# Audio_MIC.net
KiCad netlist of a schematic drawn in Altium Designer
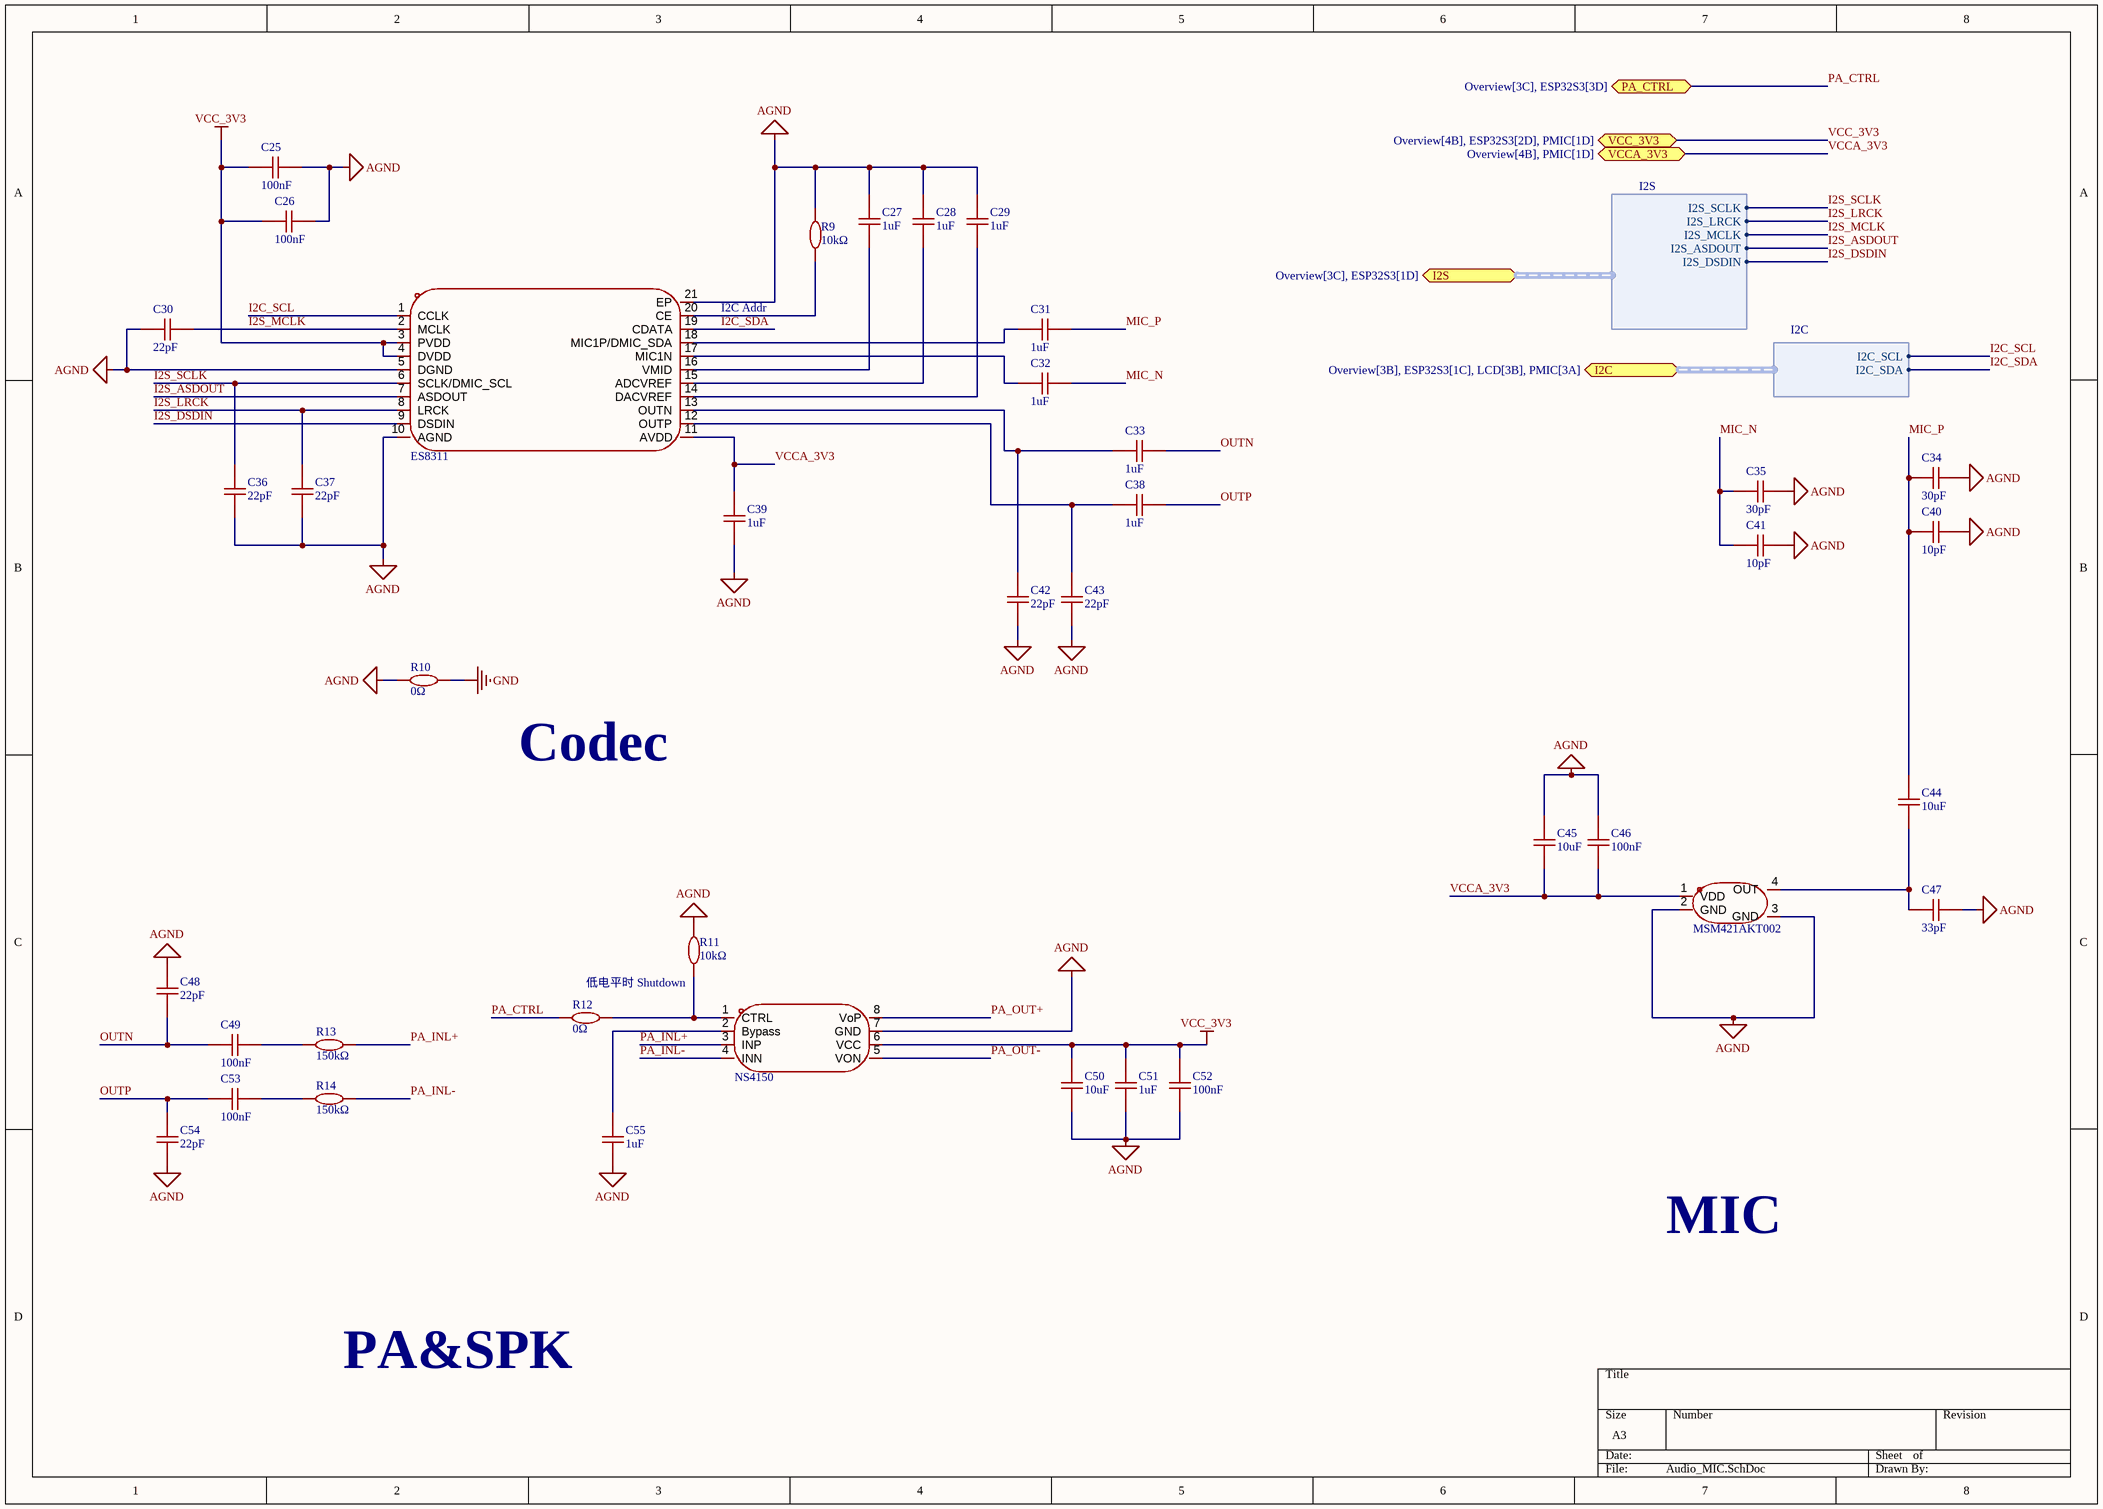
[diagram p0: Audio_MIC.SchDoc]

(export (version "E")
  (design (tool "Eeschema 10.0.6"))
  (components
    (comp (ref "C25")
      (value "100nF")
      (footprint "C0402")
      (description "50V 100nF X7R ±10% 0402 Ceramic Capacitors ROHS")
      (libsource (lib "RLC") (part "100nF"))
    )
    (comp (ref "C26")
      (value "100nF")
      (footprint "C0402")
      (description "50V 100nF X7R ±10% 0402 Ceramic Capacitors ROHS")
      (libsource (lib "RLC") (part "100nF"))
    )
    (comp (ref "C27")
      (value "1uF")
      (footprint "C0402")
      (description "50V 1uF X5R ±10% 0402 Ceramic Capacitors ROHS")
      (libsource (lib "RLC") (part "1uF"))
    )
    (comp (ref "C28")
      (value "1uF")
      (footprint "C0402")
      (description "50V 1uF X5R ±10% 0402 Ceramic Capacitors ROHS")
      (libsource (lib "RLC") (part "1uF"))
    )
    (comp (ref "C29")
      (value "1uF")
      (footprint "C0402")
      (description "50V 1uF X5R ±10% 0402 Ceramic Capacitors ROHS")
      (libsource (lib "RLC") (part "1uF"))
    )
    (comp (ref "C30")
      (value "22pF")
      (footprint "C0402")
      (description "50V 22pF C0G ±5% 0402 Ceramic Capacitors ROHS")
      (libsource (lib "RLC") (part "22pF"))
    )
    (comp (ref "C31")
      (value "1uF")
      (footprint "C0402")
      (description "50V 1uF X5R ±10% 0402 Ceramic Capacitors ROHS")
      (libsource (lib "RLC") (part "1uF"))
    )
    (comp (ref "C32")
      (value "1uF")
      (footprint "C0402")
      (description "50V 1uF X5R ±10% 0402 Ceramic Capacitors ROHS")
      (libsource (lib "RLC") (part "1uF"))
    )
    (comp (ref "C33")
      (value "1uF")
      (footprint "C0402")
      (description "50V 1uF X5R ±10% 0402 Ceramic Capacitors ROHS")
      (libsource (lib "RLC") (part "1uF"))
    )
    (comp (ref "C34")
      (value "30pF")
      (footprint "C0402")
      (description "50V 22pF C0G ±5% 0402 Ceramic Capacitors ROHS")
      (libsource (lib "RLC") (part "22pF"))
    )
    (comp (ref "C35")
      (value "30pF")
      (footprint "C0402")
      (description "50V 22pF C0G ±5% 0402 Ceramic Capacitors ROHS")
      (libsource (lib "RLC") (part "22pF"))
    )
    (comp (ref "C36")
      (value "22pF")
      (footprint "C0402")
      (description "50V 22pF C0G ±5% 0402 Ceramic Capacitors ROHS")
      (libsource (lib "RLC") (part "22pF"))
    )
    (comp (ref "C37")
      (value "22pF")
      (footprint "C0402")
      (description "50V 22pF C0G ±5% 0402 Ceramic Capacitors ROHS")
      (libsource (lib "RLC") (part "22pF"))
    )
    (comp (ref "C38")
      (value "1uF")
      (footprint "C0402")
      (description "50V 1uF X5R ±10% 0402 Ceramic Capacitors ROHS")
      (libsource (lib "RLC") (part "1uF"))
    )
    (comp (ref "C39")
      (value "1uF")
      (footprint "C0402")
      (description "50V 1uF X5R ±10% 0402 Ceramic Capacitors ROHS")
      (libsource (lib "RLC") (part "1uF"))
    )
    (comp (ref "C40")
      (value "10pF")
      (footprint "C0402")
      (description "50V 22pF C0G ±5% 0402 Ceramic Capacitors ROHS")
      (libsource (lib "RLC") (part "22pF"))
    )
    (comp (ref "C41")
      (value "10pF")
      (footprint "C0402")
      (description "50V 22pF C0G ±5% 0402 Ceramic Capacitors ROHS")
      (libsource (lib "RLC") (part "22pF"))
    )
    (comp (ref "C42")
      (value "22pF")
      (footprint "C0402")
      (description "50V 22pF C0G ±5% 0402 Ceramic Capacitors ROHS")
      (libsource (lib "RLC") (part "22pF"))
    )
    (comp (ref "C43")
      (value "22pF")
      (footprint "C0402")
      (description "50V 22pF C0G ±5% 0402 Ceramic Capacitors ROHS")
      (libsource (lib "RLC") (part "22pF"))
    )
    (comp (ref "C44")
      (value "10uF")
      (footprint "C0603")
      (description "10V 10uF X5R ±10% 0603 Ceramic Capacitors ROHS")
      (libsource (lib "RLC") (part "10uF"))
    )
    (comp (ref "C45")
      (value "10uF")
      (footprint "C0603")
      (description "10V 10uF X5R ±10% 0603 Ceramic Capacitors ROHS")
      (libsource (lib "RLC") (part "10uF"))
    )
    (comp (ref "C46")
      (value "100nF")
      (footprint "C0402")
      (description "50V 100nF X7R ±10% 0402 Ceramic Capacitors ROHS")
      (libsource (lib "RLC") (part "100nF"))
    )
    (comp (ref "C47")
      (value "33pF")
      (footprint "C0402")
      (description "50V 22pF C0G ±5% 0402 Ceramic Capacitors ROHS")
      (libsource (lib "RLC") (part "22pF"))
    )
    (comp (ref "C48")
      (value "22pF")
      (footprint "C0402")
      (description "50V 22pF C0G ±5% 0402 Ceramic Capacitors ROHS")
      (libsource (lib "RLC") (part "22pF"))
    )
    (comp (ref "C49")
      (value "100nF")
      (footprint "C0402")
      (description "50V 100nF X7R ±10% 0402 Ceramic Capacitors ROHS")
      (libsource (lib "RLC") (part "100nF"))
    )
    (comp (ref "C50")
      (value "10uF")
      (footprint "C0603")
      (description "10V 10uF X5R ±10% 0603 Ceramic Capacitors ROHS")
      (libsource (lib "RLC") (part "10uF"))
    )
    (comp (ref "C51")
      (value "1uF")
      (footprint "C0402")
      (description "50V 1uF X5R ±10% 0402 Ceramic Capacitors ROHS")
      (libsource (lib "RLC") (part "1uF"))
    )
    (comp (ref "C52")
      (value "100nF")
      (footprint "C0402")
      (description "50V 100nF X7R ±10% 0402 Ceramic Capacitors ROHS")
      (libsource (lib "RLC") (part "100nF"))
    )
    (comp (ref "C53")
      (value "100nF")
      (footprint "C0402")
      (description "50V 100nF X7R ±10% 0402 Ceramic Capacitors ROHS")
      (libsource (lib "RLC") (part "100nF"))
    )
    (comp (ref "C54")
      (value "22pF")
      (footprint "C0402")
      (description "50V 22pF C0G ±5% 0402 Ceramic Capacitors ROHS")
      (libsource (lib "RLC") (part "22pF"))
    )
    (comp (ref "C55")
      (value "1uF")
      (footprint "C0402")
      (description "50V 1uF X5R ±10% 0402 Ceramic Capacitors ROHS")
      (libsource (lib "RLC") (part "1uF"))
    )
    (comp (ref "R9")
      (value "10kΩ")
      (footprint "R0402")
      (description "62.5mW 10kΩ 50V ±100ppm/℃ Thick Film Resistor ±1% 0402 Chip Resistor - Surface Mount ROHS")
      (libsource (lib "RLC") (part "10kΩ"))
    )
    (comp (ref "R10")
      (value "0Ω")
      (footprint "R0402")
      (description "0Ω 62.5mW 50V Thick Film Resistor ±1% 0402 Chip Resistor - Surface Mount ROHS")
      (libsource (lib "RLC") (part "0Ω"))
    )
    (comp (ref "R11")
      (value "10kΩ")
      (footprint "R0402")
      (description "62.5mW 10kΩ 50V ±100ppm/℃ Thick Film Resistor ±1% 0402 Chip Resistor - Surface Mount ROHS")
      (libsource (lib "RLC") (part "10kΩ"))
    )
    (comp (ref "R12")
      (value "0Ω")
      (footprint "R0402")
      (description "0Ω 62.5mW 50V Thick Film Resistor ±1% 0402 Chip Resistor - Surface Mount ROHS")
      (libsource (lib "RLC") (part "0Ω"))
    )
    (comp (ref "R13")
      (value "150kΩ")
      (footprint "R0402")
      (description "62.5mW 150kΩ 50V ±100ppm/℃ Thick Film Resistor ±1% 0402 Chip Resistor - Surface Mount ROHS")
      (libsource (lib "RLC") (part "150kΩ"))
    )
    (comp (ref "R14")
      (value "150kΩ")
      (footprint "R0402")
      (description "62.5mW 150kΩ 50V ±100ppm/℃ Thick Film Resistor ±1% 0402 Chip Resistor - Surface Mount ROHS")
      (libsource (lib "RLC") (part "150kΩ"))
    )
    (comp (ref "U7")
      (value "ES8311")
      (footprint "WQFN-20_L3.0-W3.0-P0.40-BL-EP1.7")
      (description "低功耗单声道音频编解码器")
      (libsource (lib "IC") (part "ES8311"))
    )
    (comp (ref "U8")
      (value "MSM421AKT002")
      (footprint "LGA-4_L3.8-W3.0-P2.46-TR")
      (description "全指向型  信噪比 59dB 阻抗")
      (libsource (lib "IC") (part "MSM421AKT002"))
    )
    (comp (ref "U9")
      (value "NS4150")
      (footprint "MSOP-8_L3.0-W3.0-P0.65-LS5.0-BL")
      (description "超低EMI、无需滤波器、3W单声道D类音频功放")
      (libsource (lib "IC") (part "NS4150"))
    )
  )
  (nets
    (net (code "3") (name "/I2C_SCL") (class "Default")
      (node (ref "U7") (pin "1") (pinfunction "CCLK_1") (pintype "passive"))
    )
    (net (code "4") (name "/I2C_SDA") (class "Default")
      (node (ref "U7") (pin "19") (pinfunction "CDATA_19") (pintype "passive"))
    )
    (net (code "5") (name "/I2S_ASDOUT") (class "Default")
      (node (ref "U7") (pin "7") (pinfunction "ASDOUT_7") (pintype "passive"))
    )
    (net (code "6") (name "/I2S_DSDIN") (class "Default")
      (node (ref "U7") (pin "9") (pinfunction "DSDIN_9") (pintype "passive"))
    )
    (net (code "7") (name "/I2S_LRCK") (class "Default")
      (node (ref "C37") (pin "1") (pinfunction "1_1") (pintype "passive"))
      (node (ref "U7") (pin "8") (pinfunction "LRCK_8") (pintype "passive"))
    )
    (net (code "8") (name "/I2S_MCLK") (class "Default")
      (node (ref "C30") (pin "1") (pinfunction "1_1") (pintype "passive"))
      (node (ref "U7") (pin "2") (pinfunction "MCLK_2") (pintype "passive"))
    )
    (net (code "9") (name "/I2S_SCLK") (class "Default")
      (node (ref "C36") (pin "1") (pinfunction "1_1") (pintype "passive"))
      (node (ref "U7") (pin "6") (pinfunction "SCLK/DMIC_SCL_6") (pintype "passive"))
    )
    (net (code "10") (name "/MIC_N") (class "Default")
      (node (ref "C32") (pin "2") (pinfunction "2_2") (pintype "passive"))
      (node (ref "C35") (pin "1") (pinfunction "1_1") (pintype "passive"))
      (node (ref "C41") (pin "1") (pinfunction "1_1") (pintype "passive"))
    )
    (net (code "11") (name "/MIC_P") (class "Default")
      (node (ref "C31") (pin "2") (pinfunction "2_2") (pintype "passive"))
      (node (ref "C34") (pin "1") (pinfunction "1_1") (pintype "passive"))
      (node (ref "C40") (pin "1") (pinfunction "1_1") (pintype "passive"))
      (node (ref "C44") (pin "2") (pinfunction "2_2") (pintype "passive"))
    )
    (net (code "12") (name "/OUTN") (class "Default")
      (node (ref "C33") (pin "2") (pinfunction "2_2") (pintype "passive"))
      (node (ref "C48") (pin "2") (pinfunction "2_2") (pintype "passive"))
      (node (ref "C49") (pin "2") (pinfunction "2_2") (pintype "passive"))
    )
    (net (code "13") (name "/OUTP") (class "Default")
      (node (ref "C38") (pin "2") (pinfunction "2_2") (pintype "passive"))
      (node (ref "C53") (pin "2") (pinfunction "2_2") (pintype "passive"))
      (node (ref "C54") (pin "1") (pinfunction "1_1") (pintype "passive"))
    )
    (net (code "14") (name "/PA_CTRL") (class "Default")
      (node (ref "R12") (pin "1") (pinfunction "1_1") (pintype "passive"))
    )
    (net (code "15") (name "/PA_INL+") (class "Default")
      (node (ref "R13") (pin "2") (pinfunction "2_2") (pintype "passive"))
      (node (ref "U9") (pin "3") (pinfunction "INP_3") (pintype "passive"))
    )
    (net (code "16") (name "/PA_INL-") (class "Default")
      (node (ref "R14") (pin "2") (pinfunction "2_2") (pintype "passive"))
      (node (ref "U9") (pin "4") (pinfunction "INN_4") (pintype "passive"))
    )
    (net (code "17") (name "/PA_OUT+") (class "Default")
      (node (ref "U9") (pin "8") (pinfunction "VoP_8") (pintype "passive"))
    )
    (net (code "18") (name "/PA_OUT-") (class "Default")
      (node (ref "U9") (pin "5") (pinfunction "VON_5") (pintype "passive"))
    )
    (net (code "19") (name "/VCCA_3V3") (class "Default")
      (node (ref "C39") (pin "2") (pinfunction "2_2") (pintype "passive"))
      (node (ref "C45") (pin "1") (pinfunction "1_1") (pintype "passive"))
      (node (ref "C46") (pin "2") (pinfunction "2_2") (pintype "passive"))
      (node (ref "U7") (pin "11") (pinfunction "AVDD_11") (pintype "passive"))
      (node (ref "U8") (pin "1") (pinfunction "VDD_1") (pintype "passive"))
    )
    (net (code "22") (name "AGND") (class "Default")
      (node (ref "C25") (pin "1") (pinfunction "1_1") (pintype "passive"))
      (node (ref "C26") (pin "1") (pinfunction "1_1") (pintype "passive"))
      (node (ref "C27") (pin "2") (pinfunction "2_2") (pintype "passive"))
      (node (ref "C28") (pin "2") (pinfunction "2_2") (pintype "passive"))
      (node (ref "C29") (pin "2") (pinfunction "2_2") (pintype "passive"))
      (node (ref "C30") (pin "2") (pinfunction "2_2") (pintype "passive"))
      (node (ref "C34") (pin "2") (pinfunction "2_2") (pintype "passive"))
      (node (ref "C35") (pin "2") (pinfunction "2_2") (pintype "passive"))
      (node (ref "C36") (pin "2") (pinfunction "2_2") (pintype "passive"))
      (node (ref "C37") (pin "2") (pinfunction "2_2") (pintype "passive"))
      (node (ref "C39") (pin "1") (pinfunction "1_1") (pintype "passive"))
      (node (ref "C40") (pin "2") (pinfunction "2_2") (pintype "passive"))
      (node (ref "C41") (pin "2") (pinfunction "2_2") (pintype "passive"))
      (node (ref "C42") (pin "1") (pinfunction "1_1") (pintype "passive"))
      (node (ref "C43") (pin "1") (pinfunction "1_1") (pintype "passive"))
      (node (ref "C45") (pin "2") (pinfunction "2_2") (pintype "passive"))
      (node (ref "C46") (pin "1") (pinfunction "1_1") (pintype "passive"))
      (node (ref "C47") (pin "2") (pinfunction "2_2") (pintype "passive"))
      (node (ref "C48") (pin "1") (pinfunction "1_1") (pintype "passive"))
      (node (ref "C50") (pin "1") (pinfunction "1_1") (pintype "passive"))
      (node (ref "C51") (pin "1") (pinfunction "1_1") (pintype "passive"))
      (node (ref "C52") (pin "2") (pinfunction "2_2") (pintype "passive"))
      (node (ref "C54") (pin "2") (pinfunction "2_2") (pintype "passive"))
      (node (ref "C55") (pin "1") (pinfunction "1_1") (pintype "passive"))
      (node (ref "R10") (pin "1") (pinfunction "1_1") (pintype "passive"))
      (node (ref "R11") (pin "2") (pinfunction "2_2") (pintype "passive"))
      (node (ref "R9") (pin "2") (pinfunction "2_2") (pintype "passive"))
      (node (ref "U7") (pin "10") (pinfunction "AGND_10") (pintype "passive"))
      (node (ref "U7") (pin "21") (pinfunction "EP_21") (pintype "passive"))
      (node (ref "U7") (pin "5") (pinfunction "DGND_5") (pintype "passive"))
      (node (ref "U8") (pin "2") (pinfunction "GND_2") (pintype "passive"))
      (node (ref "U8") (pin "3") (pinfunction "GND_3") (pintype "passive"))
      (node (ref "U9") (pin "7") (pinfunction "GND_7") (pintype "passive"))
    )
    (net (code "23") (name "GND") (class "Default")
      (node (ref "R10") (pin "2") (pinfunction "2_2") (pintype "passive"))
    )
    (net (code "24") (name "Net-(C49-Pad1)") (class "Default")
      (node (ref "C49") (pin "1") (pinfunction "1_1") (pintype "passive"))
      (node (ref "R13") (pin "1") (pinfunction "1_1") (pintype "passive"))
    )
    (net (code "25") (name "Net-(C53-Pad1)") (class "Default")
      (node (ref "C53") (pin "1") (pinfunction "1_1") (pintype "passive"))
      (node (ref "R14") (pin "1") (pinfunction "1_1") (pintype "passive"))
    )
    (net (code "26") (name "Net-(U7-ADCVREF)") (class "Default")
      (node (ref "C28") (pin "1") (pinfunction "1_1") (pintype "passive"))
      (node (ref "U7") (pin "15") (pinfunction "ADCVREF_15") (pintype "passive"))
    )
    (net (code "27") (name "Net-(U7-CE)") (class "Default")
      (node (ref "R9") (pin "1") (pinfunction "1_1") (pintype "passive"))
      (node (ref "U7") (pin "20") (pinfunction "CE_20") (pintype "passive"))
    )
    (net (code "28") (name "Net-(U7-DACVREF)") (class "Default")
      (node (ref "C29") (pin "1") (pinfunction "1_1") (pintype "passive"))
      (node (ref "U7") (pin "14") (pinfunction "DACVREF_14") (pintype "passive"))
    )
    (net (code "29") (name "Net-(U7-MIC1N)") (class "Default")
      (node (ref "C32") (pin "1") (pinfunction "1_1") (pintype "passive"))
      (node (ref "U7") (pin "17") (pinfunction "MIC1N_17") (pintype "passive"))
    )
    (net (code "30") (name "Net-(U7-MIC1P{slash}DMIC_SDA)") (class "Default")
      (node (ref "C31") (pin "1") (pinfunction "1_1") (pintype "passive"))
      (node (ref "U7") (pin "18") (pinfunction "MIC1P/DMIC_SDA_18") (pintype "passive"))
    )
    (net (code "31") (name "Net-(U7-OUTN)") (class "Default")
      (node (ref "C33") (pin "1") (pinfunction "1_1") (pintype "passive"))
      (node (ref "C42") (pin "2") (pinfunction "2_2") (pintype "passive"))
      (node (ref "U7") (pin "13") (pinfunction "OUTN_13") (pintype "passive"))
    )
    (net (code "32") (name "Net-(U7-OUTP)") (class "Default")
      (node (ref "C38") (pin "1") (pinfunction "1_1") (pintype "passive"))
      (node (ref "C43") (pin "2") (pinfunction "2_2") (pintype "passive"))
      (node (ref "U7") (pin "12") (pinfunction "OUTP_12") (pintype "passive"))
    )
    (net (code "33") (name "Net-(U7-VMID)") (class "Default")
      (node (ref "C27") (pin "1") (pinfunction "1_1") (pintype "passive"))
      (node (ref "U7") (pin "16") (pinfunction "VMID_16") (pintype "passive"))
    )
    (net (code "34") (name "Net-(U8-OUT)") (class "Default")
      (node (ref "C44") (pin "1") (pinfunction "1_1") (pintype "passive"))
      (node (ref "C47") (pin "1") (pinfunction "1_1") (pintype "passive"))
      (node (ref "U8") (pin "4") (pinfunction "OUT_4") (pintype "passive"))
    )
    (net (code "35") (name "Net-(U9-Bypass)") (class "Default")
      (node (ref "C55") (pin "2") (pinfunction "2_2") (pintype "passive"))
      (node (ref "U9") (pin "2") (pinfunction "Bypass_2") (pintype "passive"))
    )
    (net (code "36") (name "Net-(U9-CTRL)") (class "Default")
      (node (ref "R11") (pin "1") (pinfunction "1_1") (pintype "passive"))
      (node (ref "R12") (pin "2") (pinfunction "2_2") (pintype "passive"))
      (node (ref "U9") (pin "1") (pinfunction "CTRL_1") (pintype "passive"))
    )
    (net (code "37") (name "VCC_3V3") (class "Default")
      (node (ref "C25") (pin "2") (pinfunction "2_2") (pintype "passive"))
      (node (ref "C26") (pin "2") (pinfunction "2_2") (pintype "passive"))
      (node (ref "C50") (pin "2") (pinfunction "2_2") (pintype "passive"))
      (node (ref "C51") (pin "2") (pinfunction "2_2") (pintype "passive"))
      (node (ref "C52") (pin "1") (pinfunction "1_1") (pintype "passive"))
      (node (ref "U7") (pin "3") (pinfunction "PVDD_3") (pintype "passive"))
      (node (ref "U7") (pin "4") (pinfunction "DVDD_4") (pintype "passive"))
      (node (ref "U9") (pin "6") (pinfunction "VCC_6") (pintype "passive"))
    )
  )
)
